# FiltroRF.net
KiCad netlist of a schematic drawn in Altium Designer
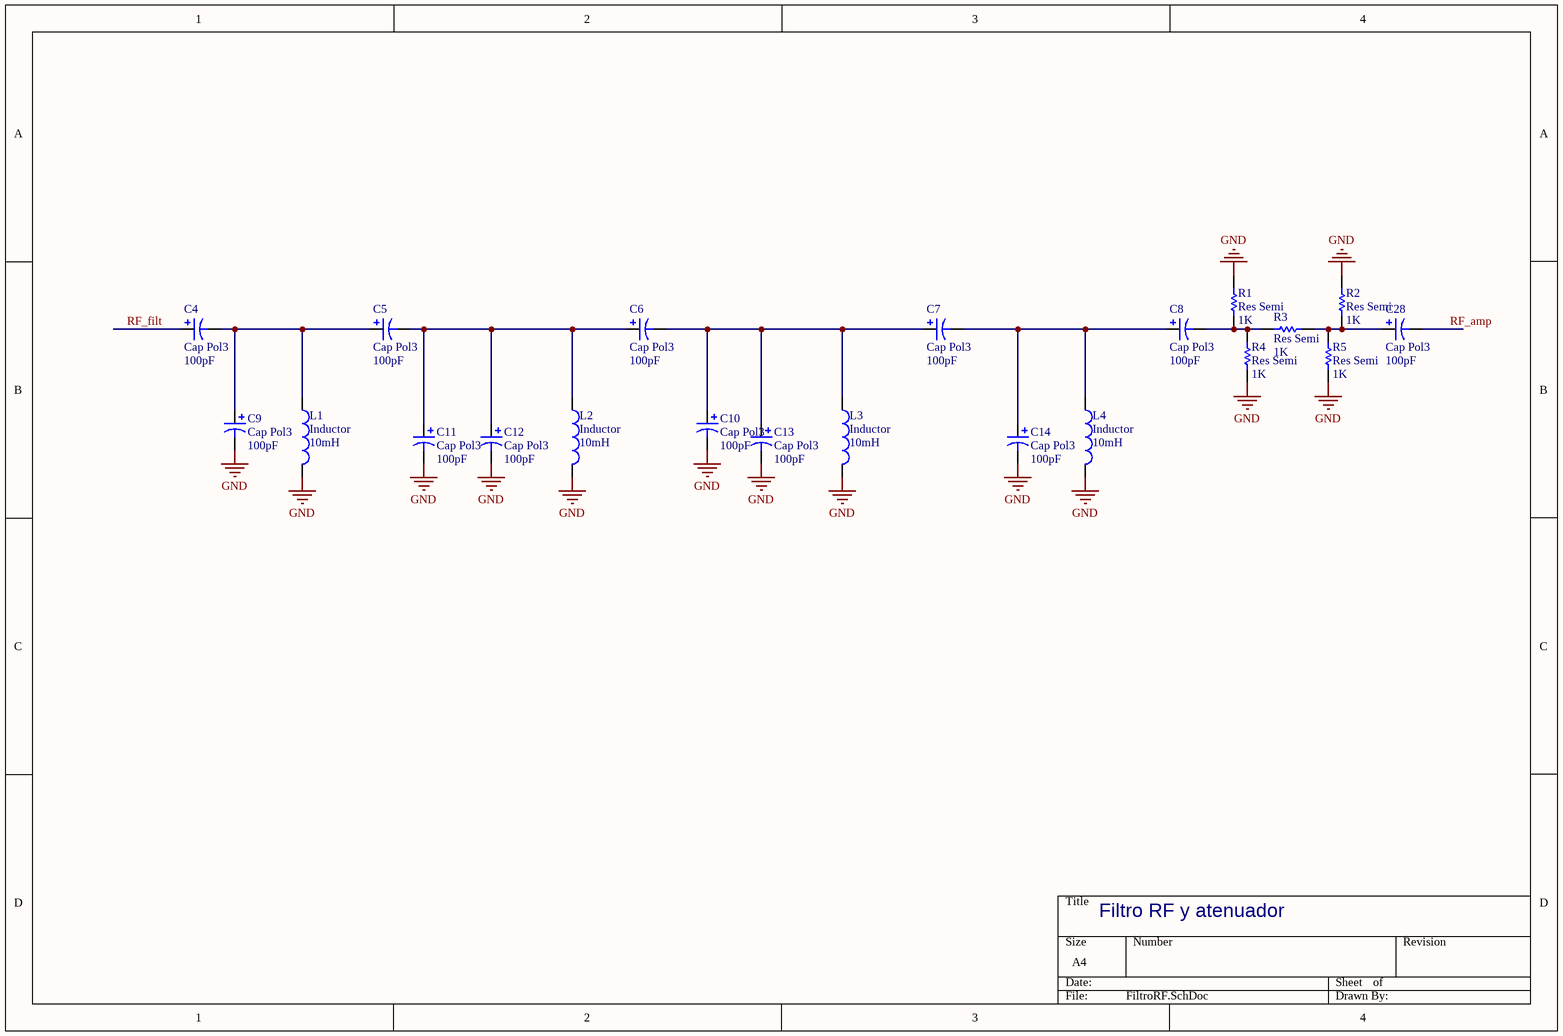
[diagram p0: FiltroRF.SchDoc]

(export (version "E")
  (design (tool "Eeschema 10.0.6"))
  (components
    (comp (ref "C4")
      (value "Cap Pol3")
      (footprint "C0805")
      (description "Polarized Capacitor (Surface Mount)")
      (fields (field (name "ALTIUM_VALUE") "100pF") (field (name "PUBLISHER") "Altium Limited"))
      (libsource (lib "Miscellaneous Devices") (part "Cap Pol3"))
    )
    (comp (ref "C5")
      (value "Cap Pol3")
      (footprint "C0805")
      (description "Polarized Capacitor (Surface Mount)")
      (fields (field (name "ALTIUM_VALUE") "100pF") (field (name "PUBLISHER") "Altium Limited"))
      (libsource (lib "Miscellaneous Devices") (part "Cap Pol3"))
    )
    (comp (ref "C6")
      (value "Cap Pol3")
      (footprint "C0805")
      (description "Polarized Capacitor (Surface Mount)")
      (fields (field (name "ALTIUM_VALUE") "100pF") (field (name "PUBLISHER") "Altium Limited"))
      (libsource (lib "Miscellaneous Devices") (part "Cap Pol3"))
    )
    (comp (ref "C7")
      (value "Cap Pol3")
      (footprint "C0805")
      (description "Polarized Capacitor (Surface Mount)")
      (fields (field (name "ALTIUM_VALUE") "100pF") (field (name "PUBLISHER") "Altium Limited"))
      (libsource (lib "Miscellaneous Devices") (part "Cap Pol3"))
    )
    (comp (ref "C8")
      (value "Cap Pol3")
      (footprint "C0805")
      (description "Polarized Capacitor (Surface Mount)")
      (fields (field (name "ALTIUM_VALUE") "100pF") (field (name "PUBLISHER") "Altium Limited"))
      (libsource (lib "Miscellaneous Devices") (part "Cap Pol3"))
    )
    (comp (ref "C9")
      (value "Cap Pol3")
      (footprint "C0805")
      (description "Polarized Capacitor (Surface Mount)")
      (fields (field (name "ALTIUM_VALUE") "100pF") (field (name "PUBLISHER") "Altium Limited"))
      (libsource (lib "Miscellaneous Devices") (part "Cap Pol3"))
    )
    (comp (ref "C10")
      (value "Cap Pol3")
      (footprint "C0805")
      (description "Polarized Capacitor (Surface Mount)")
      (fields (field (name "ALTIUM_VALUE") "100pF") (field (name "PUBLISHER") "Altium Limited"))
      (libsource (lib "Miscellaneous Devices") (part "Cap Pol3"))
    )
    (comp (ref "C11")
      (value "Cap Pol3")
      (footprint "C0805")
      (description "Polarized Capacitor (Surface Mount)")
      (fields (field (name "ALTIUM_VALUE") "100pF") (field (name "PUBLISHER") "Altium Limited"))
      (libsource (lib "Miscellaneous Devices") (part "Cap Pol3"))
    )
    (comp (ref "C12")
      (value "Cap Pol3")
      (footprint "C0805")
      (description "Polarized Capacitor (Surface Mount)")
      (fields (field (name "ALTIUM_VALUE") "100pF") (field (name "PUBLISHER") "Altium Limited"))
      (libsource (lib "Miscellaneous Devices") (part "Cap Pol3"))
    )
    (comp (ref "C13")
      (value "Cap Pol3")
      (footprint "C0805")
      (description "Polarized Capacitor (Surface Mount)")
      (fields (field (name "ALTIUM_VALUE") "100pF") (field (name "PUBLISHER") "Altium Limited"))
      (libsource (lib "Miscellaneous Devices") (part "Cap Pol3"))
    )
    (comp (ref "C14")
      (value "Cap Pol3")
      (footprint "C0805")
      (description "Polarized Capacitor (Surface Mount)")
      (fields (field (name "ALTIUM_VALUE") "100pF") (field (name "PUBLISHER") "Altium Limited"))
      (libsource (lib "Miscellaneous Devices") (part "Cap Pol3"))
    )
    (comp (ref "C28")
      (value "Cap Pol3")
      (footprint "C0805")
      (description "Polarized Capacitor (Surface Mount)")
      (fields (field (name "ALTIUM_VALUE") "100pF") (field (name "PUBLISHER") "Altium Limited"))
      (libsource (lib "Miscellaneous Devices") (part "Cap Pol3"))
    )
    (comp (ref "L1")
      (value "Inductor")
      (footprint "3261")
      (fields (field (name "ALTIUM_VALUE") "10mH") (field (name "PUBLISHER") "Altium Limited"))
      (libsource (lib "Miscellaneous Devices") (part "Inductor"))
    )
    (comp (ref "L2")
      (value "Inductor")
      (footprint "3261")
      (fields (field (name "ALTIUM_VALUE") "10mH") (field (name "PUBLISHER") "Altium Limited"))
      (libsource (lib "Miscellaneous Devices") (part "Inductor"))
    )
    (comp (ref "L3")
      (value "Inductor")
      (footprint "3261")
      (fields (field (name "ALTIUM_VALUE") "10mH") (field (name "PUBLISHER") "Altium Limited"))
      (libsource (lib "Miscellaneous Devices") (part "Inductor"))
    )
    (comp (ref "L4")
      (value "Inductor")
      (footprint "3261")
      (fields (field (name "ALTIUM_VALUE") "10mH") (field (name "PUBLISHER") "Altium Limited"))
      (libsource (lib "Miscellaneous Devices") (part "Inductor"))
    )
    (comp (ref "R1")
      (value "Res Semi")
      (footprint "2012[0805]")
      (description "Semiconductor Resistor")
      (fields (field (name "ALTIUM_VALUE") "1K") (field (name "PUBLISHER") "Altium Limited"))
      (libsource (lib "Miscellaneous Devices") (part "Res Semi"))
    )
    (comp (ref "R2")
      (value "Res Semi")
      (footprint "2012[0805]")
      (description "Semiconductor Resistor")
      (fields (field (name "ALTIUM_VALUE") "1K") (field (name "PUBLISHER") "Altium Limited"))
      (libsource (lib "Miscellaneous Devices") (part "Res Semi"))
    )
    (comp (ref "R3")
      (value "Res Semi")
      (footprint "2012[0805]")
      (description "Semiconductor Resistor")
      (fields (field (name "ALTIUM_VALUE") "1K") (field (name "PUBLISHER") "Altium Limited"))
      (libsource (lib "Miscellaneous Devices") (part "Res Semi"))
    )
    (comp (ref "R4")
      (value "Res Semi")
      (footprint "2012[0805]")
      (description "Semiconductor Resistor")
      (fields (field (name "ALTIUM_VALUE") "1K") (field (name "PUBLISHER") "Altium Limited"))
      (libsource (lib "Miscellaneous Devices") (part "Res Semi"))
    )
    (comp (ref "R5")
      (value "Res Semi")
      (footprint "2012[0805]")
      (description "Semiconductor Resistor")
      (fields (field (name "ALTIUM_VALUE") "1K") (field (name "PUBLISHER") "Altium Limited"))
      (libsource (lib "Miscellaneous Devices") (part "Res Semi"))
    )
  )
  (nets
    (net (code "1") (name "/RF_amp") (class "Default")
      (node (ref "C28") (pin "2") (pinfunction "2_2") (pintype "passive"))
    )
    (net (code "2") (name "/RF_filt") (class "Default")
      (node (ref "C4") (pin "1") (pinfunction "1_1") (pintype "passive"))
    )
    (net (code "3") (name "GND") (class "Default")
      (node (ref "C10") (pin "2") (pinfunction "2_2") (pintype "passive"))
      (node (ref "C11") (pin "2") (pinfunction "2_2") (pintype "passive"))
      (node (ref "C12") (pin "2") (pinfunction "2_2") (pintype "passive"))
      (node (ref "C13") (pin "2") (pinfunction "2_2") (pintype "passive"))
      (node (ref "C14") (pin "2") (pinfunction "2_2") (pintype "passive"))
      (node (ref "C9") (pin "2") (pinfunction "2_2") (pintype "passive"))
      (node (ref "L1") (pin "2") (pinfunction "2_2") (pintype "passive"))
      (node (ref "L2") (pin "2") (pinfunction "2_2") (pintype "passive"))
      (node (ref "L3") (pin "2") (pinfunction "2_2") (pintype "passive"))
      (node (ref "L4") (pin "2") (pinfunction "2_2") (pintype "passive"))
      (node (ref "R1") (pin "1") (pinfunction "1_1") (pintype "passive"))
      (node (ref "R2") (pin "1") (pinfunction "1_1") (pintype "passive"))
      (node (ref "R4") (pin "1") (pinfunction "1_1") (pintype "passive"))
      (node (ref "R5") (pin "1") (pinfunction "1_1") (pintype "passive"))
    )
    (net (code "4") (name "Net-(C4-Pad2)") (class "Default")
      (node (ref "C4") (pin "2") (pinfunction "2_2") (pintype "passive"))
      (node (ref "C5") (pin "1") (pinfunction "1_1") (pintype "passive"))
      (node (ref "C9") (pin "1") (pinfunction "1_1") (pintype "passive"))
      (node (ref "L1") (pin "1") (pinfunction "1_1") (pintype "passive"))
    )
    (net (code "5") (name "Net-(C8-Pad2)") (class "Default")
      (node (ref "C8") (pin "2") (pinfunction "2_2") (pintype "passive"))
      (node (ref "R1") (pin "2") (pinfunction "2_2") (pintype "passive"))
      (node (ref "R3") (pin "2") (pinfunction "2_2") (pintype "passive"))
      (node (ref "R4") (pin "2") (pinfunction "2_2") (pintype "passive"))
    )
    (net (code "6") (name "Net-(C10-Pad1)") (class "Default")
      (node (ref "C10") (pin "1") (pinfunction "1_1") (pintype "passive"))
      (node (ref "C13") (pin "1") (pinfunction "1_1") (pintype "passive"))
      (node (ref "C6") (pin "2") (pinfunction "2_2") (pintype "passive"))
      (node (ref "C7") (pin "1") (pinfunction "1_1") (pintype "passive"))
      (node (ref "L3") (pin "1") (pinfunction "1_1") (pintype "passive"))
    )
    (net (code "7") (name "Net-(C11-Pad1)") (class "Default")
      (node (ref "C11") (pin "1") (pinfunction "1_1") (pintype "passive"))
      (node (ref "C12") (pin "1") (pinfunction "1_1") (pintype "passive"))
      (node (ref "C5") (pin "2") (pinfunction "2_2") (pintype "passive"))
      (node (ref "C6") (pin "1") (pinfunction "1_1") (pintype "passive"))
      (node (ref "L2") (pin "1") (pinfunction "1_1") (pintype "passive"))
    )
    (net (code "8") (name "Net-(C14-Pad1)") (class "Default")
      (node (ref "C14") (pin "1") (pinfunction "1_1") (pintype "passive"))
      (node (ref "C7") (pin "2") (pinfunction "2_2") (pintype "passive"))
      (node (ref "C8") (pin "1") (pinfunction "1_1") (pintype "passive"))
      (node (ref "L4") (pin "1") (pinfunction "1_1") (pintype "passive"))
    )
    (net (code "9") (name "Net-(C28-Pad1)") (class "Default")
      (node (ref "C28") (pin "1") (pinfunction "1_1") (pintype "passive"))
      (node (ref "R2") (pin "2") (pinfunction "2_2") (pintype "passive"))
      (node (ref "R3") (pin "1") (pinfunction "1_1") (pintype "passive"))
      (node (ref "R5") (pin "2") (pinfunction "2_2") (pintype "passive"))
    )
  )
)
